# CD4060BM.net
KiCad netlist of a schematic drawn in Altium Designer
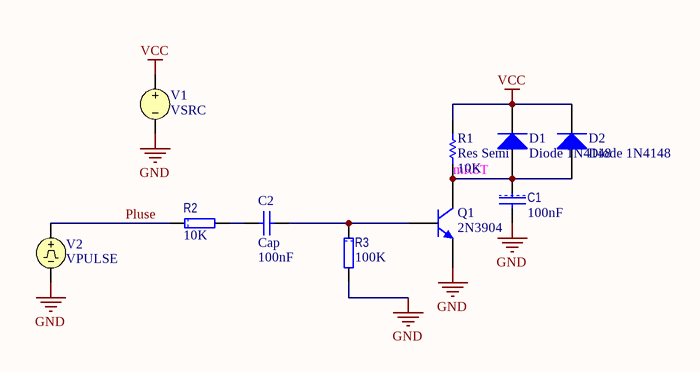
[diagram p0: CD4060BM_硬件定时器_仿真.SchDoc]

(export (version "E")
  (design (tool "Eeschema 10.0.6"))
  (components
    (comp (ref "C1")
      (value "100nF")
      (footprint "1608[0603]C")
      (description "多层陶瓷电容器MLCC - SMD/SMT 0603 0.1uF 50volts X7R 10%")
      (fields (field (name "MANUFACTURER") "TDK") (field (name "MANUFACTURER PART NUMBER") "C1608X7R1H104K"))
      (libsource (lib "*") (part "CAP"))
    )
    (comp (ref "C2")
      (value "Cap")
      (footprint "RAD-0.3")
      (description "Capacitor")
      (fields (field (name "ALTIUM_VALUE") "100nF") (field (name "PUBLISHER") "Altium Limited"))
      (libsource (lib "Miscellaneous Devices") (part "Cap"))
    )
    (comp (ref "D1")
      (value "Diode 1N4148")
      (footprint "DO-35")
      (description "High Conductance Fast Diode")
      (fields (field (name "PUBLISHER") "Altium Limited"))
      (libsource (lib "Miscellaneous Devices") (part "Diode 1N4148"))
    )
    (comp (ref "D2")
      (value "Diode 1N4148")
      (footprint "DO-35")
      (description "High Conductance Fast Diode")
      (fields (field (name "PUBLISHER") "Altium Limited"))
      (libsource (lib "Miscellaneous Devices") (part "Diode 1N4148"))
    )
    (comp (ref "Q1")
      (value "2N3904")
      (footprint "SOT-23_N")
      (description "NPN General Purpose Amplifier")
      (libsource (lib "Miscellaneous Devices") (part "2N3904"))
    )
    (comp (ref "R1")
      (value "Res Semi")
      (footprint "AXIAL-0.5")
      (description "Semiconductor Resistor")
      (fields (field (name "ALTIUM_VALUE") "10K") (field (name "PUBLISHER") "Altium Limited"))
      (libsource (lib "Miscellaneous Devices") (part "Res Semi"))
    )
    (comp (ref "R2")
      (value "10K")
      (footprint "1608[0603]R")
      (description "厚膜电阻器 - SMD 1/10watt 100Kohms 1%")
      (fields
        (field (name "MANUFACTURER") "Vishay / Dale")
        (field (name "MANUFACTURER PART NUMBER") "CRCW0603100KFKEA")
      )
      (libsource (lib "100K 1%") (part "RES"))
    )
    (comp (ref "R3")
      (value "100K")
      (footprint "1608[0603]R")
      (description "厚膜电阻器 - SMD 1/10watt 100Kohms 1%")
      (fields
        (field (name "MANUFACTURER") "Vishay / Dale")
        (field (name "MANUFACTURER PART NUMBER") "CRCW0603100KFKEA")
      )
      (libsource (lib "100K 1%") (part "RES"))
    )
    (comp (ref "V1")
      (value "VSRC")
      (description "Voltage Source")
      (fields (field (name "PUBLISHER") "Altium Limited"))
      (libsource (lib "Simulation Sources") (part "VSRC"))
    )
    (comp (ref "V2")
      (value "VPULSE")
      (description "Pulse Voltage Source")
      (fields (field (name "PUBLISHER") "Altium Limited"))
      (libsource (lib "Simulation Sources") (part "VPULSE"))
    )
  )
  (nets
    (net (code "1") (name "/Pluse") (class "Default")
      (node (ref "R2") (pin "1") (pinfunction "1_1") (pintype "passive"))
      (node (ref "V2") (pin "1") (pinfunction "1_1") (pintype "passive"))
    )
    (net (code "2") (name "/mRST") (class "Default")
      (node (ref "C1") (pin "1") (pinfunction "1_1") (pintype "passive"))
      (node (ref "D1") (pin "1") (pinfunction "A_1") (pintype "passive"))
      (node (ref "D2") (pin "1") (pinfunction "A_1") (pintype "passive"))
      (node (ref "Q1") (pin "3") (pinfunction "C_3") (pintype "passive"))
      (node (ref "R1") (pin "1") (pinfunction "1_1") (pintype "passive"))
    )
    (net (code "3") (name "GND") (class "Default")
      (node (ref "C1") (pin "2") (pinfunction "2_2") (pintype "passive"))
      (node (ref "Q1") (pin "1") (pinfunction "E_1") (pintype "passive"))
      (node (ref "R3") (pin "2") (pinfunction "2_2") (pintype "passive"))
      (node (ref "V1") (pin "2") (pinfunction "2_2") (pintype "passive"))
      (node (ref "V2") (pin "2") (pinfunction "2_2") (pintype "passive"))
    )
    (net (code "4") (name "Net-(C2-Pad1)") (class "Default")
      (node (ref "C2") (pin "1") (pinfunction "1_1") (pintype "passive"))
      (node (ref "R2") (pin "2") (pinfunction "2_2") (pintype "passive"))
    )
    (net (code "5") (name "Net-(Q1-B)") (class "Default")
      (node (ref "C2") (pin "2") (pinfunction "2_2") (pintype "passive"))
      (node (ref "Q1") (pin "2") (pinfunction "B_2") (pintype "passive"))
      (node (ref "R3") (pin "1") (pinfunction "1_1") (pintype "passive"))
    )
    (net (code "6") (name "VCC") (class "Default")
      (node (ref "D1") (pin "2") (pinfunction "K_2") (pintype "passive"))
      (node (ref "D2") (pin "2") (pinfunction "K_2") (pintype "passive"))
      (node (ref "R1") (pin "2") (pinfunction "2_2") (pintype "passive"))
      (node (ref "V1") (pin "1") (pinfunction "1_1") (pintype "passive"))
    )
  )
)
